# respirho675.net
KiCad netlist of a schematic drawn in EAGLE
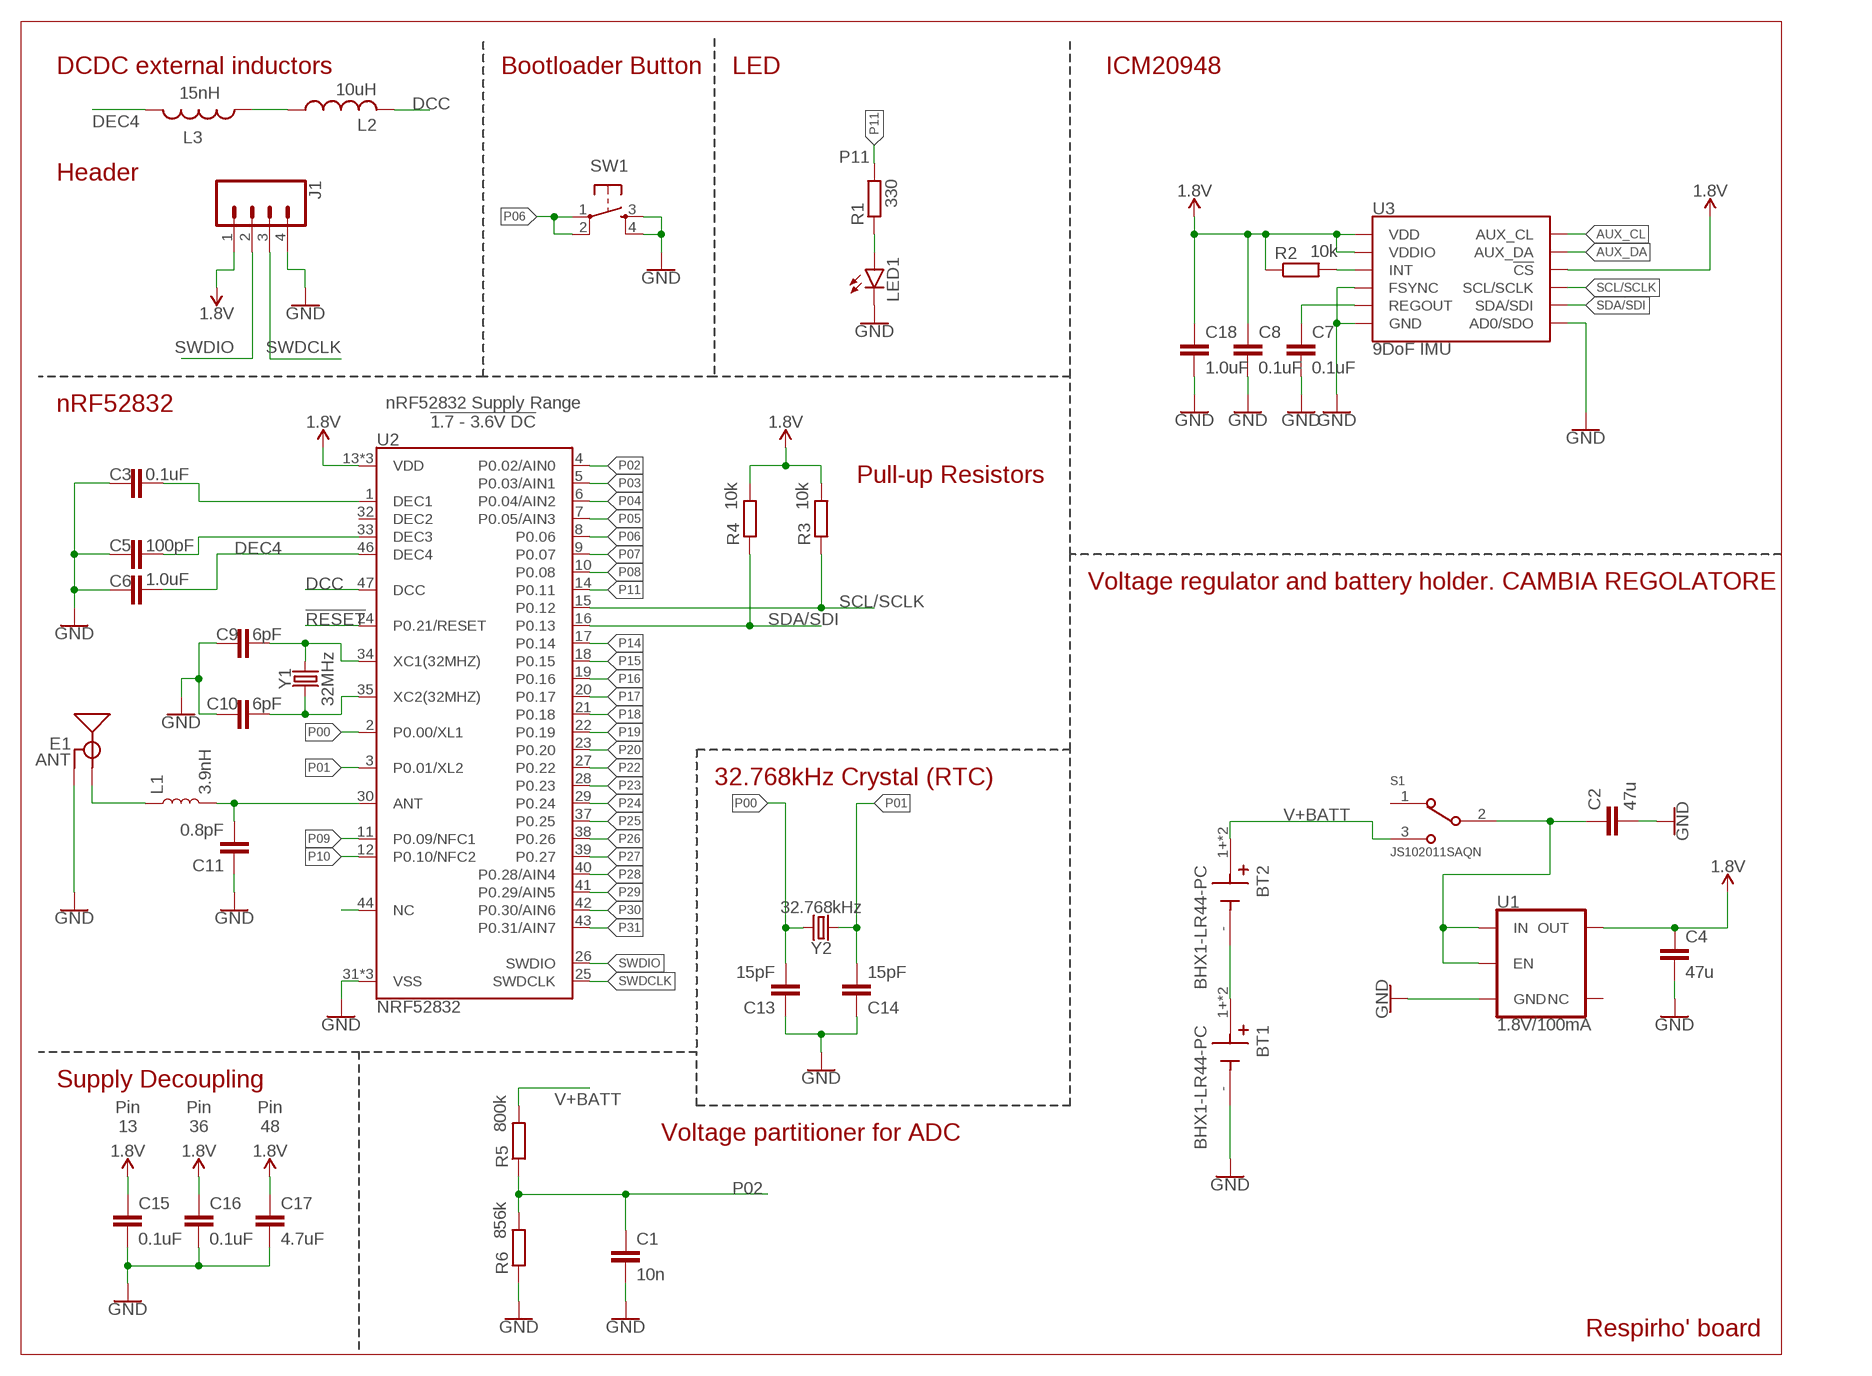
[diagram p0: schematic, sheet 1]

(export (version "E")
  (design (tool "Eeschema 10.0.6"))
  (components
    (comp (ref "BT1")
      (value "BHX1-LR44-PC")
      (footprint "eagle-import:BAT_BHX1-LR44-PC")
      (fields (field (name "DIGI-KEY_PART_NUMBER") "BHX1-LR44-PC-G-ND") (field (name "MF") "MPD"))
      (libsource (lib "eagle-import") (part "BHX1-LR44-PC"))
    )
    (comp (ref "BT2")
      (value "BHX1-LR44-PC")
      (footprint "eagle-import:BAT_BHX1-LR44-PC")
      (fields (field (name "DIGI-KEY_PART_NUMBER") "BHX1-LR44-PC-G-ND") (field (name "MF") "MPD"))
      (libsource (lib "eagle-import") (part "BHX1-LR44-PC"))
    )
    (comp (ref "C1")
      (value "10n")
      (footprint "eagle-import:C1206")
      (libsource (lib "eagle-import") (part "C-EUC1206"))
    )
    (comp (ref "C2")
      (value "47u")
      (footprint "eagle-import:C1206")
      (libsource (lib "eagle-import") (part "C-EUC1206"))
    )
    (comp (ref "C3")
      (value "0.1uF")
      (footprint "eagle-import:0402")
      (libsource (lib "eagle-import") (part "0.1UF-0402-16V-10%"))
    )
    (comp (ref "C4")
      (value "47u")
      (footprint "eagle-import:C1206")
      (libsource (lib "eagle-import") (part "C-EUC1206"))
    )
    (comp (ref "C5")
      (value "100pF")
      (footprint "eagle-import:0402")
      (libsource (lib "eagle-import") (part "100PF-0402-50V-5%"))
    )
    (comp (ref "C6")
      (value "1.0uF")
      (footprint "eagle-import:0402")
      (libsource (lib "eagle-import") (part "1.0UF-0402-16V-10%"))
    )
    (comp (ref "C7")
      (value "0.1uF")
      (footprint "eagle-import:0603")
      (libsource (lib "eagle-import") (part "0.1UF-0603-25V-5%"))
    )
    (comp (ref "C8")
      (value "0.1uF")
      (footprint "eagle-import:0603")
      (libsource (lib "eagle-import") (part "0.1UF-0603-25V-5%"))
    )
    (comp (ref "C9")
      (value "6pF")
      (footprint "eagle-import:0402")
      (libsource (lib "eagle-import") (part "6PF-0402-50V-0.5%"))
    )
    (comp (ref "C10")
      (value "6pF")
      (footprint "eagle-import:0402")
      (libsource (lib "eagle-import") (part "6PF-0402-50V-0.5%"))
    )
    (comp (ref "C11")
      (value "0.8pF")
      (footprint "eagle-import:0402")
      (libsource (lib "eagle-import") (part "0.8PF-0402-50V-0.1PF"))
    )
    (comp (ref "C13")
      (value "15pF")
      (footprint "eagle-import:0402")
      (libsource (lib "eagle-import") (part "15PF-0402-50V-5%"))
    )
    (comp (ref "C14")
      (value "15pF")
      (footprint "eagle-import:0402")
      (libsource (lib "eagle-import") (part "15PF-0402-50V-5%"))
    )
    (comp (ref "C15")
      (value "0.1uF")
      (footprint "eagle-import:0402")
      (libsource (lib "eagle-import") (part "0.1UF-0402-16V-10%"))
    )
    (comp (ref "C16")
      (value "0.1uF")
      (footprint "eagle-import:0402")
      (libsource (lib "eagle-import") (part "0.1UF-0402-16V-10%"))
    )
    (comp (ref "C17")
      (value "4.7uF")
      (footprint "eagle-import:0603")
      (libsource (lib "eagle-import") (part "4.7UF0603"))
    )
    (comp (ref "C18")
      (value "1.0uF")
      (footprint "eagle-import:0603")
      (libsource (lib "eagle-import") (part "1.0UF-0603-16V-10%-X7R"))
    )
    (comp (ref "E1")
      (value "ANT")
      (footprint "eagle-import:TRACE_ANTENNA_2.4GHZ_15.2MM")
      (libsource (lib "eagle-import") (part "ANTENNA-GROUNDEDTRACE-15.2MM"))
    )
    (comp (ref "J1")
      (value "CONN_04PTH")
      (footprint "eagle-import:1X04")
      (libsource (lib "eagle-import") (part "CONN_04PTH"))
    )
    (comp (ref "L1")
      (value "3.9nH")
      (footprint "eagle-import:0402")
      (libsource (lib "eagle-import") (part "INDUCTOR-0402-3.9NH"))
    )
    (comp (ref "L2")
      (value "10uH")
      (footprint "eagle-import:RESC0603_L")
      (libsource (lib "eagle-import") (part "INDUCTOR_0603_L"))
    )
    (comp (ref "L3")
      (value "15nH")
      (footprint "eagle-import:INDC1005X55N")
      (fields
        (field (name "DIGI-KEY_PART_NUMBER") "490-2625-1-ND")
        (field (name "MF") "Murata Electronics")
        (field (name "MP") "LQG15HS15NJ02D")
      )
      (libsource (lib "eagle-import") (part "LQG15HS15NJ02D"))
    )
    (comp (ref "LED1")
      (value "LEDCHIPLED_1206")
      (footprint "eagle-import:CHIPLED_1206")
      (libsource (lib "eagle-import") (part "LEDCHIPLED_1206"))
    )
    (comp (ref "R1")
      (value "330")
      (footprint "eagle-import:R0805")
      (libsource (lib "eagle-import") (part "R-EU_R0805"))
    )
    (comp (ref "R2")
      (value "10k")
      (footprint "eagle-import:R0805")
      (libsource (lib "eagle-import") (part "R-EU_R0805"))
    )
    (comp (ref "R3")
      (value "10k")
      (footprint "eagle-import:R0805")
      (libsource (lib "eagle-import") (part "R-EU_R0805"))
    )
    (comp (ref "R4")
      (value "10k")
      (footprint "eagle-import:R0805")
      (libsource (lib "eagle-import") (part "R-EU_R0805"))
    )
    (comp (ref "R5")
      (value "800k")
      (footprint "eagle-import:R0805")
      (libsource (lib "eagle-import") (part "R-EU_R0805"))
    )
    (comp (ref "R6")
      (value "856k")
      (footprint "eagle-import:R0805")
      (libsource (lib "eagle-import") (part "R-EU_R0805"))
    )
    (comp (ref "S1")
      (value "JS102011SAQN")
      (footprint "eagle-import:SW_JS102011SAQN")
      (fields (field (name "DIGI-KEY_PART_NUMBER") "401-1999-1-ND") (field (name "MF") "C&K"))
      (libsource (lib "eagle-import") (part "JS102011SAQN"))
    )
    (comp (ref "SW1")
      (value "SWITCH_SPST_4_PINRECT")
      (footprint "eagle-import:TACTILE_SWITCH_SMD_4.6X2.8MM")
      (libsource (lib "eagle-import") (part "SWITCH_SPST_4_PINRECT"))
    )
    (comp (ref "U1")
      (value "1.8V/100mA")
      (footprint "eagle-import:SC70")
      (libsource (lib "eagle-import") (part "V_REG_SP6214-1.8V"))
    )
    (comp (ref "U2")
      (value "NRF52832")
      (footprint "eagle-import:QFN48-6X6MM")
      (libsource (lib "eagle-import") (part "NRF52832"))
    )
    (comp (ref "U3")
      (value "9DoF IMU")
      (footprint "eagle-import:QFN24-3X3")
      (libsource (lib "eagle-import") (part "ICM-20948"))
    )
    (comp (ref "Y1")
      (value "32MHz")
      (footprint "eagle-import:CRYSTAL-SMD-2.0X1.6MM")
      (libsource (lib "eagle-import") (part "CRYSTAL-32MHZ-SMD-2.0X1.6MM"))
    )
    (comp (ref "Y2")
      (value "32.768kHz")
      (footprint "eagle-import:CRYSTAL-SMD-3.2X1.5MM")
      (libsource (lib "eagle-import") (part "CRYSTAL-32.768KHZSMD-3.2X1.5"))
    )
  )
  (nets
    (net (code "1") (name "/DCC") (class "Default")
      (node (ref "L2") (pin "2") (pinfunction "2_2") (pintype "passive"))
      (node (ref "U2") (pin "47") (pinfunction "DCC_47") (pintype "bidirectional"))
    )
    (net (code "2") (name "/DEC4") (class "Default")
      (node (ref "C6") (pin "2") (pinfunction "2_2") (pintype "passive"))
      (node (ref "L3") (pin "2") (pinfunction "2_2") (pintype "passive"))
      (node (ref "U2") (pin "46") (pinfunction "DEC4_46") (pintype "bidirectional"))
    )
    (net (code "3") (name "/V+BATT") (class "Default")
      (node (ref "BT2") (pin "1+") (pinfunction "+_1+") (pintype "passive"))
      (node (ref "BT2") (pin "2+") (pinfunction "+_2+") (pintype "passive"))
      (node (ref "R5") (pin "2") (pinfunction "2_2") (pintype "passive"))
      (node (ref "S1") (pin "3") (pinfunction "3_3") (pintype "passive"))
    )
    (net (code "4") (name "/~{RESET}") (class "Default")
      (node (ref "U2") (pin "24") (pinfunction "P0.21/RESET_24") (pintype "bidirectional"))
    )
    (net (code "5") (name "1.8V") (class "Default")
      (node (ref "C15") (pin "1") (pinfunction "1_1") (pintype "passive"))
      (node (ref "C16") (pin "1") (pinfunction "1_1") (pintype "passive"))
      (node (ref "C17") (pin "1") (pinfunction "1_1") (pintype "passive"))
      (node (ref "C18") (pin "1") (pinfunction "1_1") (pintype "passive"))
      (node (ref "C4") (pin "1") (pinfunction "1_1") (pintype "passive"))
      (node (ref "C8") (pin "1") (pinfunction "1_1") (pintype "passive"))
      (node (ref "J1") (pin "1") (pinfunction "1_1") (pintype "passive"))
      (node (ref "R2") (pin "1") (pinfunction "1_1") (pintype "passive"))
      (node (ref "R3") (pin "2") (pinfunction "2_2") (pintype "passive"))
      (node (ref "R4") (pin "2") (pinfunction "2_2") (pintype "passive"))
      (node (ref "U1") (pin "5") (pinfunction "OUT_5") (pintype "passive"))
      (node (ref "U2") (pin "13") (pinfunction "VDD_13") (pintype "bidirectional"))
      (node (ref "U2") (pin "36") (pinfunction "VDD_36") (pintype "bidirectional"))
      (node (ref "U2") (pin "48") (pinfunction "VDD_48") (pintype "bidirectional"))
      (node (ref "U3") (pin "13") (pinfunction "VDD_13") (pintype "bidirectional"))
      (node (ref "U3") (pin "22") (pinfunction "~{CS}_22") (pintype "bidirectional"))
      (node (ref "U3") (pin "8") (pinfunction "VDDIO_8") (pintype "bidirectional"))
    )
    (net (code "6") (name "AUX_CL") (class "Default")
      (node (ref "U3") (pin "7") (pinfunction "AUX_CL_7") (pintype "bidirectional"))
    )
    (net (code "7") (name "AUX_DA") (class "Default")
      (node (ref "U3") (pin "21") (pinfunction "AUX_DA_21") (pintype "bidirectional"))
    )
    (net (code "8") (name "GND") (class "Default")
      (node (ref "BT1") (pin "-") (pinfunction "-_-") (pintype "passive"))
      (node (ref "C1") (pin "2") (pinfunction "2_2") (pintype "passive"))
      (node (ref "C10") (pin "2") (pinfunction "2_2") (pintype "passive"))
      (node (ref "C11") (pin "1") (pinfunction "1_1") (pintype "passive"))
      (node (ref "C13") (pin "1") (pinfunction "1_1") (pintype "passive"))
      (node (ref "C14") (pin "1") (pinfunction "1_1") (pintype "passive"))
      (node (ref "C15") (pin "2") (pinfunction "2_2") (pintype "passive"))
      (node (ref "C16") (pin "2") (pinfunction "2_2") (pintype "passive"))
      (node (ref "C17") (pin "2") (pinfunction "2_2") (pintype "passive"))
      (node (ref "C18") (pin "2") (pinfunction "2_2") (pintype "passive"))
      (node (ref "C2") (pin "2") (pinfunction "2_2") (pintype "passive"))
      (node (ref "C3") (pin "1") (pinfunction "1_1") (pintype "passive"))
      (node (ref "C4") (pin "2") (pinfunction "2_2") (pintype "passive"))
      (node (ref "C5") (pin "1") (pinfunction "1_1") (pintype "passive"))
      (node (ref "C6") (pin "1") (pinfunction "1_1") (pintype "passive"))
      (node (ref "C7") (pin "2") (pinfunction "2_2") (pintype "passive"))
      (node (ref "C8") (pin "2") (pinfunction "2_2") (pintype "passive"))
      (node (ref "C9") (pin "1") (pinfunction "1_1") (pintype "passive"))
      (node (ref "E1") (pin "GND") (pinfunction "GND_GND") (pintype "bidirectional"))
      (node (ref "J1") (pin "4") (pinfunction "4_4") (pintype "passive"))
      (node (ref "LED1") (pin "C") (pinfunction "C_C") (pintype "passive"))
      (node (ref "R6") (pin "1") (pinfunction "1_1") (pintype "passive"))
      (node (ref "SW1") (pin "3") (pinfunction "3_3") (pintype "passive"))
      (node (ref "SW1") (pin "4") (pinfunction "4_4") (pintype "passive"))
      (node (ref "U1") (pin "2") (pinfunction "GND_2") (pintype "input"))
      (node (ref "U2") (pin "31") (pinfunction "VSS_31") (pintype "bidirectional"))
      (node (ref "U2") (pin "45") (pinfunction "VSS_45") (pintype "bidirectional"))
      (node (ref "U2") (pin "EP") (pinfunction "VSS_EP") (pintype "bidirectional"))
      (node (ref "U3") (pin "11") (pinfunction "FSYNC_11") (pintype "bidirectional"))
      (node (ref "U3") (pin "18") (pinfunction "GND_18") (pintype "bidirectional"))
      (node (ref "U3") (pin "20") (pinfunction "GND_20") (pintype "bidirectional"))
      (node (ref "U3") (pin "9") (pinfunction "AD0/SDO_9") (pintype "bidirectional"))
    )
    (net (code "9") (name "Net-(BT1-+-Pad1+)") (class "Default")
      (node (ref "BT1") (pin "1+") (pinfunction "+_1+") (pintype "passive"))
      (node (ref "BT1") (pin "2+") (pinfunction "+_2+") (pintype "passive"))
      (node (ref "BT2") (pin "-") (pinfunction "-_-") (pintype "passive"))
    )
    (net (code "10") (name "Net-(E1-SIGNAL)") (class "Default")
      (node (ref "E1") (pin "ANT") (pinfunction "SIGNAL_ANT") (pintype "bidirectional"))
      (node (ref "L1") (pin "1") (pinfunction "1_1") (pintype "passive"))
    )
    (net (code "11") (name "Net-(L2-Pad1)") (class "Default")
      (node (ref "L2") (pin "1") (pinfunction "1_1") (pintype "passive"))
      (node (ref "L3") (pin "1") (pinfunction "1_1") (pintype "passive"))
    )
    (net (code "12") (name "Net-(LED1-PadA)") (class "Default")
      (node (ref "LED1") (pin "A") (pinfunction "A_A") (pintype "passive"))
      (node (ref "R1") (pin "1") (pinfunction "1_1") (pintype "passive"))
    )
    (net (code "13") (name "Net-(U1-EN)") (class "Default")
      (node (ref "C2") (pin "1") (pinfunction "1_1") (pintype "passive"))
      (node (ref "S1") (pin "2") (pinfunction "2_2") (pintype "passive"))
      (node (ref "U1") (pin "1") (pinfunction "IN_1") (pintype "input"))
      (node (ref "U1") (pin "3") (pinfunction "EN_3") (pintype "input"))
    )
    (net (code "14") (name "Net-(U2-ANT)") (class "Default")
      (node (ref "C11") (pin "2") (pinfunction "2_2") (pintype "passive"))
      (node (ref "L1") (pin "2") (pinfunction "2_2") (pintype "passive"))
      (node (ref "U2") (pin "30") (pinfunction "ANT_30") (pintype "bidirectional"))
    )
    (net (code "15") (name "Net-(U2-DEC1)") (class "Default")
      (node (ref "C3") (pin "2") (pinfunction "2_2") (pintype "passive"))
      (node (ref "U2") (pin "1") (pinfunction "DEC1_1") (pintype "bidirectional"))
    )
    (net (code "16") (name "Net-(U2-DEC3)") (class "Default")
      (node (ref "C5") (pin "2") (pinfunction "2_2") (pintype "passive"))
      (node (ref "U2") (pin "33") (pinfunction "DEC3_33") (pintype "bidirectional"))
    )
    (net (code "17") (name "Net-(U2-XC1(32MHZ))") (class "Default")
      (node (ref "C9") (pin "2") (pinfunction "2_2") (pintype "passive"))
      (node (ref "U2") (pin "34") (pinfunction "XC1(32MHZ)_34") (pintype "bidirectional"))
      (node (ref "Y1") (pin "3") (pinfunction "2_3") (pintype "passive"))
    )
    (net (code "18") (name "Net-(U2-XC2(32MHZ))") (class "Default")
      (node (ref "C10") (pin "1") (pinfunction "1_1") (pintype "passive"))
      (node (ref "U2") (pin "35") (pinfunction "XC2(32MHZ)_35") (pintype "bidirectional"))
      (node (ref "Y1") (pin "1") (pinfunction "1_1") (pintype "passive"))
    )
    (net (code "19") (name "Net-(U3-INT)") (class "Default")
      (node (ref "R2") (pin "2") (pinfunction "2_2") (pintype "passive"))
      (node (ref "U3") (pin "12") (pinfunction "INT_12") (pintype "bidirectional"))
    )
    (net (code "20") (name "Net-(U3-REGOUT)") (class "Default")
      (node (ref "C7") (pin "1") (pinfunction "1_1") (pintype "passive"))
      (node (ref "U3") (pin "10") (pinfunction "REGOUT_10") (pintype "bidirectional"))
    )
    (net (code "21") (name "P00") (class "Default")
      (node (ref "C13") (pin "2") (pinfunction "2_2") (pintype "passive"))
      (node (ref "U2") (pin "2") (pinfunction "P0.00/XL1_2") (pintype "bidirectional"))
      (node (ref "Y2") (pin "P$2") (pinfunction "2_P$2") (pintype "passive"))
    )
    (net (code "22") (name "P01") (class "Default")
      (node (ref "C14") (pin "2") (pinfunction "2_2") (pintype "passive"))
      (node (ref "U2") (pin "3") (pinfunction "P0.01/XL2_3") (pintype "bidirectional"))
      (node (ref "Y2") (pin "P$1") (pinfunction "1_P$1") (pintype "passive"))
    )
    (net (code "23") (name "P02") (class "Default")
      (node (ref "C1") (pin "1") (pinfunction "1_1") (pintype "passive"))
      (node (ref "R5") (pin "1") (pinfunction "1_1") (pintype "passive"))
      (node (ref "R6") (pin "2") (pinfunction "2_2") (pintype "passive"))
      (node (ref "U2") (pin "4") (pinfunction "P0.02/AIN0_4") (pintype "bidirectional"))
    )
    (net (code "24") (name "P03") (class "Default")
      (node (ref "U2") (pin "5") (pinfunction "P0.03/AIN1_5") (pintype "bidirectional"))
    )
    (net (code "25") (name "P04") (class "Default")
      (node (ref "U2") (pin "6") (pinfunction "P0.04/AIN2_6") (pintype "bidirectional"))
    )
    (net (code "26") (name "P05") (class "Default")
      (node (ref "U2") (pin "7") (pinfunction "P0.05/AIN3_7") (pintype "bidirectional"))
    )
    (net (code "27") (name "P06") (class "Default")
      (node (ref "SW1") (pin "1") (pinfunction "1_1") (pintype "passive"))
      (node (ref "SW1") (pin "2") (pinfunction "2_2") (pintype "passive"))
      (node (ref "U2") (pin "8") (pinfunction "P0.06_8") (pintype "bidirectional"))
    )
    (net (code "28") (name "P07") (class "Default")
      (node (ref "U2") (pin "9") (pinfunction "P0.07_9") (pintype "bidirectional"))
    )
    (net (code "29") (name "P08") (class "Default")
      (node (ref "U2") (pin "10") (pinfunction "P0.08_10") (pintype "bidirectional"))
    )
    (net (code "30") (name "P09") (class "Default")
      (node (ref "U2") (pin "11") (pinfunction "P0.09/NFC1_11") (pintype "bidirectional"))
    )
    (net (code "31") (name "P10") (class "Default")
      (node (ref "U2") (pin "12") (pinfunction "P0.10/NFC2_12") (pintype "bidirectional"))
    )
    (net (code "32") (name "P11") (class "Default")
      (node (ref "R1") (pin "2") (pinfunction "2_2") (pintype "passive"))
      (node (ref "U2") (pin "14") (pinfunction "P0.11_14") (pintype "bidirectional"))
    )
    (net (code "33") (name "P14") (class "Default")
      (node (ref "U2") (pin "17") (pinfunction "P0.14_17") (pintype "bidirectional"))
    )
    (net (code "34") (name "P15") (class "Default")
      (node (ref "U2") (pin "18") (pinfunction "P0.15_18") (pintype "bidirectional"))
    )
    (net (code "35") (name "P16") (class "Default")
      (node (ref "U2") (pin "19") (pinfunction "P0.16_19") (pintype "bidirectional"))
    )
    (net (code "36") (name "P17") (class "Default")
      (node (ref "U2") (pin "20") (pinfunction "P0.17_20") (pintype "bidirectional"))
    )
    (net (code "37") (name "P18") (class "Default")
      (node (ref "U2") (pin "21") (pinfunction "P0.18_21") (pintype "bidirectional"))
    )
    (net (code "38") (name "P19") (class "Default")
      (node (ref "U2") (pin "22") (pinfunction "P0.19_22") (pintype "bidirectional"))
    )
    (net (code "39") (name "P20") (class "Default")
      (node (ref "U2") (pin "23") (pinfunction "P0.20_23") (pintype "bidirectional"))
    )
    (net (code "40") (name "P22") (class "Default")
      (node (ref "U2") (pin "27") (pinfunction "P0.22_27") (pintype "bidirectional"))
    )
    (net (code "41") (name "P23") (class "Default")
      (node (ref "U2") (pin "28") (pinfunction "P0.23_28") (pintype "bidirectional"))
    )
    (net (code "42") (name "P24") (class "Default")
      (node (ref "U2") (pin "29") (pinfunction "P0.24_29") (pintype "bidirectional"))
    )
    (net (code "43") (name "P25") (class "Default")
      (node (ref "U2") (pin "37") (pinfunction "P0.25_37") (pintype "bidirectional"))
    )
    (net (code "44") (name "P26") (class "Default")
      (node (ref "U2") (pin "38") (pinfunction "P0.26_38") (pintype "bidirectional"))
    )
    (net (code "45") (name "P27") (class "Default")
      (node (ref "U2") (pin "39") (pinfunction "P0.27_39") (pintype "bidirectional"))
    )
    (net (code "46") (name "P28") (class "Default")
      (node (ref "U2") (pin "40") (pinfunction "P0.28/AIN4_40") (pintype "bidirectional"))
    )
    (net (code "47") (name "P29") (class "Default")
      (node (ref "U2") (pin "41") (pinfunction "P0.29/AIN5_41") (pintype "bidirectional"))
    )
    (net (code "48") (name "P30") (class "Default")
      (node (ref "U2") (pin "42") (pinfunction "P0.30/AIN6_42") (pintype "bidirectional"))
    )
    (net (code "49") (name "P31") (class "Default")
      (node (ref "U2") (pin "43") (pinfunction "P0.31/AIN7_43") (pintype "bidirectional"))
    )
    (net (code "50") (name "SCL{slash}SCLK") (class "Default")
      (node (ref "R3") (pin "1") (pinfunction "1_1") (pintype "passive"))
      (node (ref "U2") (pin "15") (pinfunction "P0.12_15") (pintype "bidirectional"))
      (node (ref "U3") (pin "23") (pinfunction "SCL/SCLK_23") (pintype "bidirectional"))
    )
    (net (code "51") (name "SDA{slash}SDI") (class "Default")
      (node (ref "R4") (pin "1") (pinfunction "1_1") (pintype "passive"))
      (node (ref "U2") (pin "16") (pinfunction "P0.13_16") (pintype "bidirectional"))
      (node (ref "U3") (pin "24") (pinfunction "SDA/SDI_24") (pintype "bidirectional"))
    )
    (net (code "52") (name "SWDCLK") (class "Default")
      (node (ref "J1") (pin "3") (pinfunction "3_3") (pintype "passive"))
      (node (ref "U2") (pin "25") (pinfunction "SWDCLK_25") (pintype "bidirectional"))
    )
    (net (code "53") (name "SWDIO") (class "Default")
      (node (ref "J1") (pin "2") (pinfunction "2_2") (pintype "passive"))
      (node (ref "U2") (pin "26") (pinfunction "SWDIO_26") (pintype "bidirectional"))
    )
    (net (code "54") (name "unconnected-(S1-Pad1)") (class "Default")
      (node (ref "S1") (pin "1") (pinfunction "1_1") (pintype "passive"))
    )
    (net (code "55") (name "unconnected-(U1-NC-Pad4)") (class "Default")
      (node (ref "U1") (pin "4") (pinfunction "NC_4") (pintype "no_connect"))
    )
    (net (code "56") (name "unconnected-(U2-DEC2-Pad32)") (class "Default")
      (node (ref "U2") (pin "32") (pinfunction "DEC2_32") (pintype "bidirectional"))
    )
    (net (code "57") (name "unconnected-(U2-NC-Pad44)") (class "Default")
      (node (ref "U2") (pin "44") (pinfunction "NC_44") (pintype "bidirectional"))
    )
  )
)
